# 5_LED.net
KiCad netlist of a schematic drawn in Altium Designer
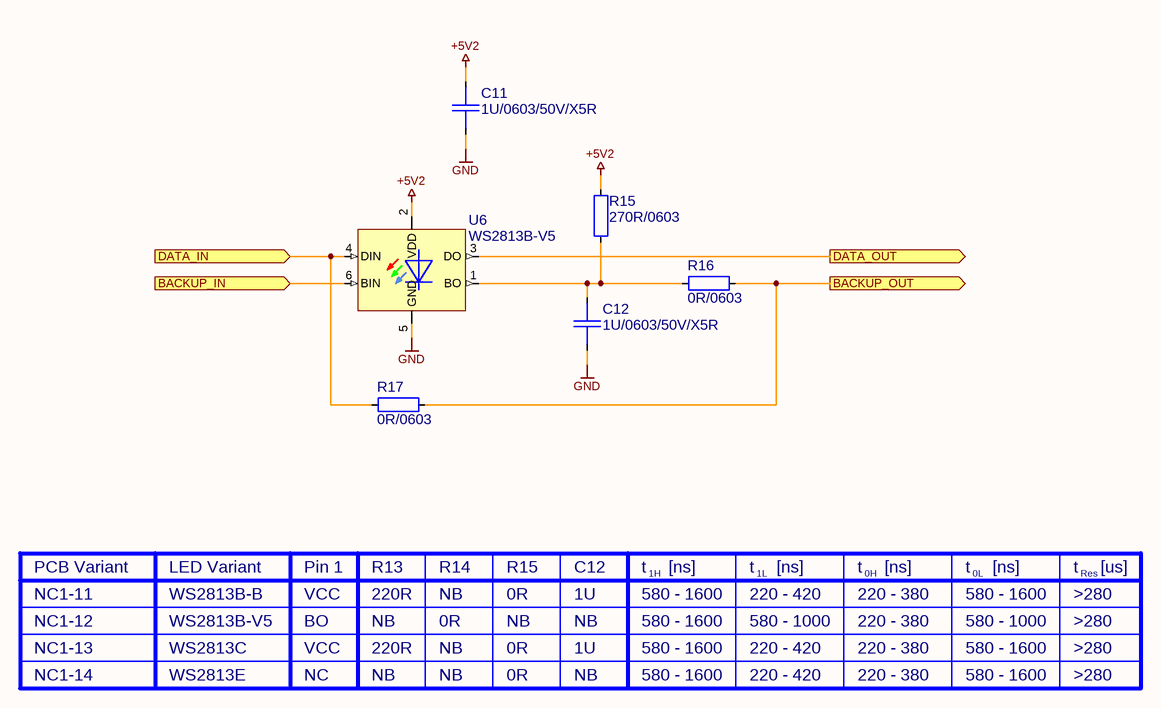
[diagram p0: [5] LED.SchDoc]

(export (version "E")
  (design (tool "Eeschema 10.0.6"))
  (components
    (comp (ref "C11")
      (value "1U/0603/50V/X5R")
      (footprint "CAP0603_X7R")
      (description "CAP SM 0603 1.0uF 50V X5R")
      (fields (field (name "MANUFACTURER") "GENERIC"))
      (libsource (lib "daniw_altium_lib") (part "C"))
    )
    (comp (ref "C12")
      (value "1U/0603/50V/X5R")
      (footprint "CAP0603_X7R")
      (description "CAP SM 0603 1.0uF 50V X5R")
      (fields (field (name "MANUFACTURER") "GENERIC"))
      (libsource (lib "daniw_altium_lib") (part "C"))
    )
    (comp (ref "R15")
      (value "270R/0603")
      (footprint "R0603-0.40-WW")
      (description "RES SM 0603 270R")
      (fields (field (name "MANUFACTURER") "GENERIC"))
      (libsource (lib "daniw_altium_lib") (part "R"))
    )
    (comp (ref "R16")
      (value "0R/0603")
      (footprint "R0603-0.40-WW")
      (description "RES SM 0603 0R")
      (fields (field (name "MANUFACTURER") "GENERIC"))
      (libsource (lib "daniw_altium_lib") (part "R"))
    )
    (comp (ref "R17")
      (value "0R/0603")
      (footprint "R0603-0.40-WW")
      (description "RES SM 0603 0R")
      (fields (field (name "MANUFACTURER") "GENERIC"))
      (libsource (lib "daniw_altium_lib") (part "R"))
    )
    (comp (ref "U6")
      (value "WS2813B-V5")
      (footprint "LEDM5050X165-6-SE")
      (description "Intelligent control LED integrated light source with backup Pin")
      (fields (field (name "MANUFACTURER") "WorldSemi"))
      (libsource (lib "daniw_altium_lib") (part "WS2813_BO"))
    )
  )
  (nets
    (net (code "1") (name "+5V2") (class "Default")
      (node (ref "C11") (pin "1") (pinfunction "1_1") (pintype "passive"))
      (node (ref "R15") (pin "1") (pinfunction "1_1") (pintype "passive"))
      (node (ref "U6") (pin "2") (pinfunction "VDD_2") (pintype "passive"))
    )
    (net (code "2") (name "/BACKUP_IN") (class "Default")
      (node (ref "U6") (pin "6") (pinfunction "BIN_6") (pintype "input"))
    )
    (net (code "3") (name "/BACKUP_OUT") (class "Default")
      (node (ref "R16") (pin "2") (pinfunction "2_2") (pintype "passive"))
      (node (ref "R17") (pin "2") (pinfunction "2_2") (pintype "passive"))
    )
    (net (code "4") (name "/DATA_IN") (class "Default")
      (node (ref "R17") (pin "1") (pinfunction "1_1") (pintype "passive"))
      (node (ref "U6") (pin "4") (pinfunction "DIN_4") (pintype "input"))
    )
    (net (code "5") (name "/DATA_OUT") (class "Default")
      (node (ref "U6") (pin "3") (pinfunction "DO_3") (pintype "output"))
    )
    (net (code "6") (name "GND") (class "Default")
      (node (ref "C11") (pin "2") (pinfunction "2_2") (pintype "passive"))
      (node (ref "C12") (pin "2") (pinfunction "2_2") (pintype "passive"))
      (node (ref "U6") (pin "5") (pinfunction "GND_5") (pintype "passive"))
    )
    (net (code "7") (name "Net-(U6-BO)") (class "Default")
      (node (ref "C12") (pin "1") (pinfunction "1_1") (pintype "passive"))
      (node (ref "R15") (pin "2") (pinfunction "2_2") (pintype "passive"))
      (node (ref "R16") (pin "1") (pinfunction "1_1") (pintype "passive"))
      (node (ref "U6") (pin "1") (pinfunction "BO_1") (pintype "output"))
    )
  )
)
